# Month.net
KiCad netlist of a schematic drawn in Altium Designer
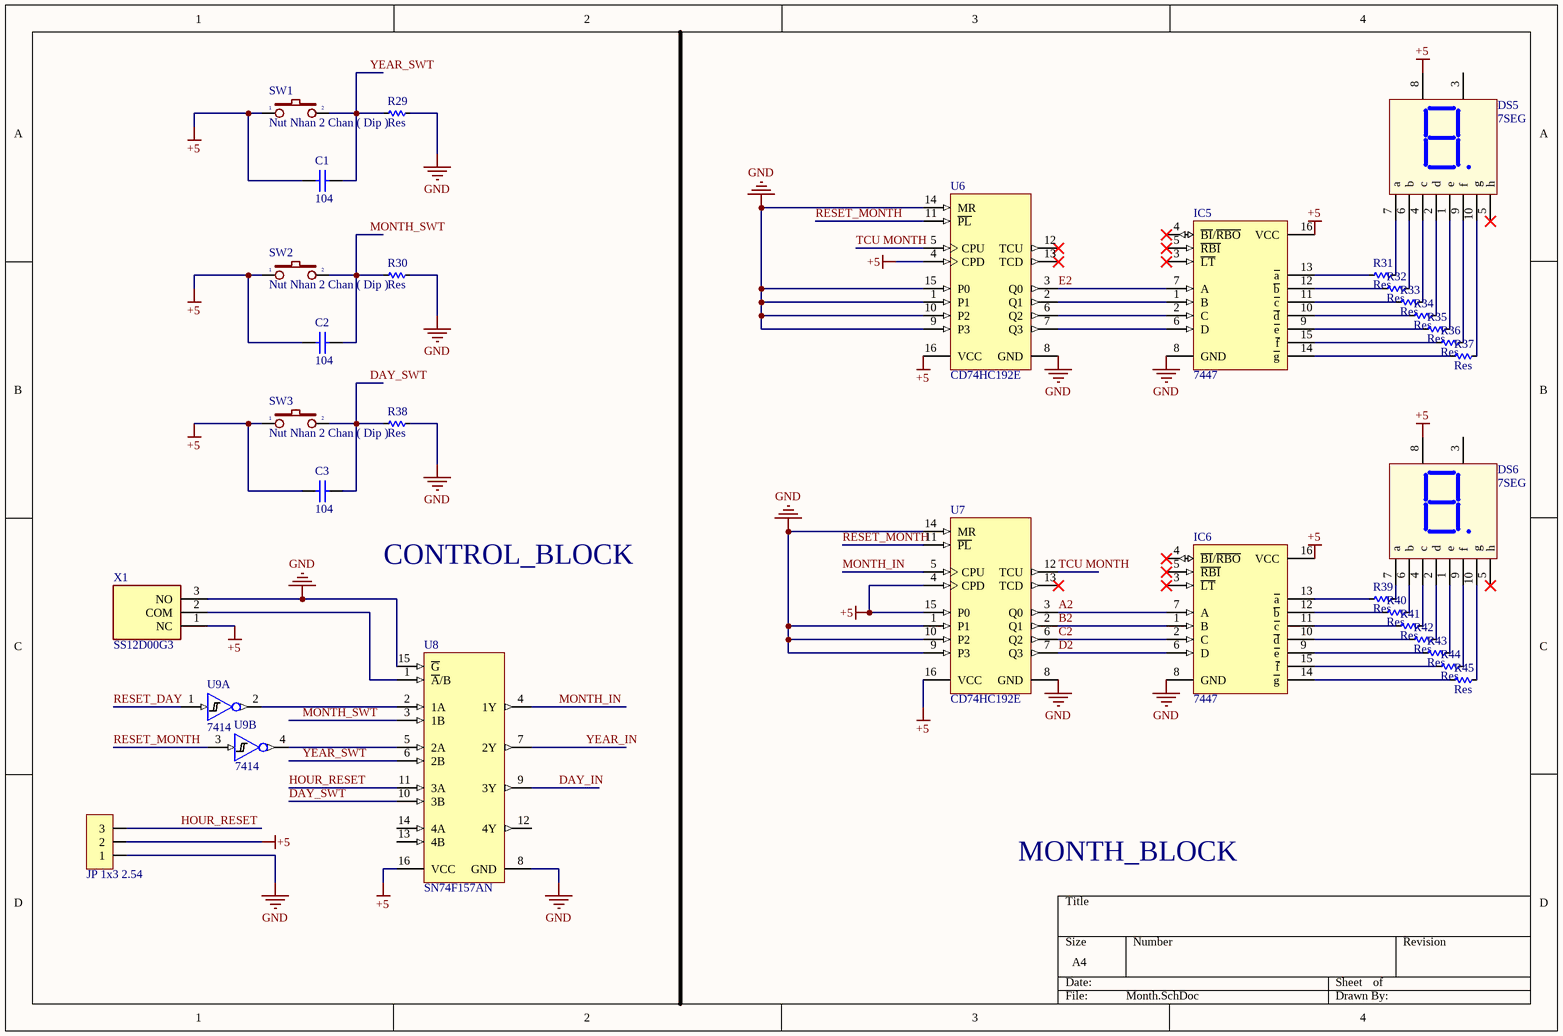
[diagram p0: Month.SchDoc]

(export (version "E")
  (design (tool "Eeschema 10.0.6"))
  (components
    (comp (ref "C1")
      (value "104")
      (footprint "tu gom")
      (description "Cắm")
      (libsource (lib "Tu dien") (part "Tu gom 104 50V"))
    )
    (comp (ref "C2")
      (value "104")
      (footprint "tu gom")
      (description "Cắm")
      (libsource (lib "Tu dien") (part "Tu gom 104 50V"))
    )
    (comp (ref "C3")
      (value "104")
      (footprint "tu gom")
      (description "Cắm")
      (libsource (lib "Tu dien") (part "Tu gom 104 50V"))
    )
    (comp (ref "DS5")
      (value "7SEG")
      (footprint "LED7SEG-1-0.56")
      (description "14.2 mm General Purpose Blue 7-Segment Display: CC, RH DP, Gray Surface")
      (fields (field (name "PUBLISHER") "Altium Limited"))
      (libsource (lib "Clock_Schlib1") (part "LED7SEG-1"))
    )
    (comp (ref "DS6")
      (value "7SEG")
      (footprint "LED7SEG-1-0.56")
      (description "14.2 mm General Purpose Blue 7-Segment Display: CC, RH DP, Gray Surface")
      (fields (field (name "PUBLISHER") "Altium Limited"))
      (libsource (lib "Clock_Schlib1") (part "LED7SEG-1"))
    )
    (comp (ref "IC5")
      (value "7447")
      (footprint "DIP16")
      (description "BCD to 7-Segment Decoder/Driver")
      (libsource (lib "Clock_Schlib1") (part "7447"))
    )
    (comp (ref "IC6")
      (value "7447")
      (footprint "DIP16")
      (description "BCD to 7-Segment Decoder/Driver")
      (libsource (lib "Clock_Schlib1") (part "7447"))
    )
    (comp (ref "JP1")
      (value "JP 1x3 2.54")
      (footprint "JP 1x3 CT")
      (description "Cắm")
      (libsource (lib "Jump") (part "JP 1x3 2.54 Cai Thang"))
    )
    (comp (ref "R29")
      (value "Res")
      (footprint "RES-1/4W")
      (fields
        (field (name "MANUFACTURER") "Generic Components")
        (field (name "PUBLISHER") "Altium Hobart Technology Centre")
      )
      (libsource (lib "Clock_Schlib1") (part "Res"))
    )
    (comp (ref "R30")
      (value "Res")
      (footprint "RES-1/4W")
      (fields
        (field (name "MANUFACTURER") "Generic Components")
        (field (name "PUBLISHER") "Altium Hobart Technology Centre")
      )
      (libsource (lib "Clock_Schlib1") (part "Res"))
    )
    (comp (ref "R31")
      (value "Res")
      (footprint "RES-1/4W")
      (fields
        (field (name "MANUFACTURER") "Generic Components")
        (field (name "PUBLISHER") "Altium Hobart Technology Centre")
      )
      (libsource (lib "Clock_Schlib1") (part "Res"))
    )
    (comp (ref "R32")
      (value "Res")
      (footprint "RES-1/4W")
      (fields
        (field (name "MANUFACTURER") "Generic Components")
        (field (name "PUBLISHER") "Altium Hobart Technology Centre")
      )
      (libsource (lib "Clock_Schlib1") (part "Res"))
    )
    (comp (ref "R33")
      (value "Res")
      (footprint "RES-1/4W")
      (fields
        (field (name "MANUFACTURER") "Generic Components")
        (field (name "PUBLISHER") "Altium Hobart Technology Centre")
      )
      (libsource (lib "Clock_Schlib1") (part "Res"))
    )
    (comp (ref "R34")
      (value "Res")
      (footprint "RES-1/4W")
      (fields
        (field (name "MANUFACTURER") "Generic Components")
        (field (name "PUBLISHER") "Altium Hobart Technology Centre")
      )
      (libsource (lib "Clock_Schlib1") (part "Res"))
    )
    (comp (ref "R35")
      (value "Res")
      (footprint "RES-1/4W")
      (fields
        (field (name "MANUFACTURER") "Generic Components")
        (field (name "PUBLISHER") "Altium Hobart Technology Centre")
      )
      (libsource (lib "Clock_Schlib1") (part "Res"))
    )
    (comp (ref "R36")
      (value "Res")
      (footprint "RES-1/4W")
      (fields
        (field (name "MANUFACTURER") "Generic Components")
        (field (name "PUBLISHER") "Altium Hobart Technology Centre")
      )
      (libsource (lib "Clock_Schlib1") (part "Res"))
    )
    (comp (ref "R37")
      (value "Res")
      (footprint "RES-1/4W")
      (fields
        (field (name "MANUFACTURER") "Generic Components")
        (field (name "PUBLISHER") "Altium Hobart Technology Centre")
      )
      (libsource (lib "Clock_Schlib1") (part "Res"))
    )
    (comp (ref "R38")
      (value "Res")
      (footprint "RES-1/4W")
      (fields
        (field (name "MANUFACTURER") "Generic Components")
        (field (name "PUBLISHER") "Altium Hobart Technology Centre")
      )
      (libsource (lib "Clock_Schlib1") (part "Res"))
    )
    (comp (ref "R39")
      (value "Res")
      (footprint "RES-1/4W")
      (fields
        (field (name "MANUFACTURER") "Generic Components")
        (field (name "PUBLISHER") "Altium Hobart Technology Centre")
      )
      (libsource (lib "Clock_Schlib1") (part "Res"))
    )
    (comp (ref "R40")
      (value "Res")
      (footprint "RES-1/4W")
      (fields
        (field (name "MANUFACTURER") "Generic Components")
        (field (name "PUBLISHER") "Altium Hobart Technology Centre")
      )
      (libsource (lib "Clock_Schlib1") (part "Res"))
    )
    (comp (ref "R41")
      (value "Res")
      (footprint "RES-1/4W")
      (fields
        (field (name "MANUFACTURER") "Generic Components")
        (field (name "PUBLISHER") "Altium Hobart Technology Centre")
      )
      (libsource (lib "Clock_Schlib1") (part "Res"))
    )
    (comp (ref "R42")
      (value "Res")
      (footprint "RES-1/4W")
      (fields
        (field (name "MANUFACTURER") "Generic Components")
        (field (name "PUBLISHER") "Altium Hobart Technology Centre")
      )
      (libsource (lib "Clock_Schlib1") (part "Res"))
    )
    (comp (ref "R43")
      (value "Res")
      (footprint "RES-1/4W")
      (fields
        (field (name "MANUFACTURER") "Generic Components")
        (field (name "PUBLISHER") "Altium Hobart Technology Centre")
      )
      (libsource (lib "Clock_Schlib1") (part "Res"))
    )
    (comp (ref "R44")
      (value "Res")
      (footprint "RES-1/4W")
      (fields
        (field (name "MANUFACTURER") "Generic Components")
        (field (name "PUBLISHER") "Altium Hobart Technology Centre")
      )
      (libsource (lib "Clock_Schlib1") (part "Res"))
    )
    (comp (ref "R45")
      (value "Res")
      (footprint "RES-1/4W")
      (fields
        (field (name "MANUFACTURER") "Generic Components")
        (field (name "PUBLISHER") "Altium Hobart Technology Centre")
      )
      (libsource (lib "Clock_Schlib1") (part "Res"))
    )
    (comp (ref "SW1")
      (value "Nut Nhan 2 Chan ( Dip )")
      (footprint "SW2")
      (description "Cắm")
      (libsource (lib "THU VIEN SCH") (part "Nut Nhan 2 Chan ( Dip )"))
    )
    (comp (ref "SW2")
      (value "Nut Nhan 2 Chan ( Dip )")
      (footprint "SW2")
      (description "Cắm")
      (libsource (lib "THU VIEN SCH") (part "Nut Nhan 2 Chan ( Dip )"))
    )
    (comp (ref "SW3")
      (value "Nut Nhan 2 Chan ( Dip )")
      (footprint "SW2")
      (description "Cắm")
      (libsource (lib "THU VIEN SCH") (part "Nut Nhan 2 Chan ( Dip )"))
    )
    (comp (ref "U6")
      (value "CD74HC192E")
      (footprint "N0016A")
      (fields
        (field (name "GENERIC PART NUMBER") "CD74HC192")
        (field (name "MANUFACTURER") "Texas Instruments")
      )
      (libsource (lib "Clock_Schlib1") (part "74192"))
    )
    (comp (ref "U7")
      (value "CD74HC192E")
      (footprint "N0016A")
      (fields
        (field (name "GENERIC PART NUMBER") "CD74HC192")
        (field (name "MANUFACTURER") "Texas Instruments")
      )
      (libsource (lib "Clock_Schlib1") (part "74192"))
    )
    (comp (ref "U8")
      (value "SN74F157AN")
      (footprint "N0016A")
      (description "Quadruple 2-Line To 1-Line Data Selectors/Multiplexers, N0016A, TUBE")
      (fields
        (field (name "MANUFACTURER") "Texas Instruments")
        (field (name "GENERIC PART NUMBER") "SN74F157A")
      )
      (libsource (lib "Altium Content Vault") (part "TI-XXX4XXXX15XX-16"))
    )
    (comp (ref "U9")
      (value "7414")
      (footprint "DIP14")
      (description "IC, M74HC04M, Hex Inverter, SO-14")
      (libsource (lib "Clock_Schlib1") (part "7414"))
    )
    (comp (ref "X1")
      (value "SS12D00G3")
      (footprint "SS12D00G3")
      (description "3 Pin Toggle Switch")
      (libsource (lib "Clock_Schlib1") (part "SS12D00G3"))
    )
  )
  (nets
    (net (code "1") (name "+5") (class "Default")
      (node (ref "C1") (pin "2") (pinfunction "2_2") (pintype "passive"))
      (node (ref "C2") (pin "2") (pinfunction "2_2") (pintype "passive"))
      (node (ref "C3") (pin "2") (pinfunction "2_2") (pintype "passive"))
      (node (ref "DS5") (pin "8") (pinfunction "Vcc_8") (pintype "passive"))
      (node (ref "DS6") (pin "8") (pinfunction "Vcc_8") (pintype "passive"))
      (node (ref "IC5") (pin "16") (pinfunction "VCC_16") (pintype "power_in"))
      (node (ref "IC6") (pin "16") (pinfunction "VCC_16") (pintype "power_in"))
      (node (ref "JP1") (pin "2") (pinfunction "2_2") (pintype "passive"))
      (node (ref "SW1") (pin "1") (pinfunction "1_1") (pintype "passive"))
      (node (ref "SW2") (pin "1") (pinfunction "1_1") (pintype "passive"))
      (node (ref "SW3") (pin "1") (pinfunction "1_1") (pintype "passive"))
      (node (ref "U6") (pin "16") (pinfunction "VCC_16") (pintype "power_in"))
      (node (ref "U6") (pin "4") (pinfunction "CPD_4") (pintype "input"))
      (node (ref "U7") (pin "15") (pinfunction "P0_15") (pintype "input"))
      (node (ref "U7") (pin "16") (pinfunction "VCC_16") (pintype "power_in"))
      (node (ref "U7") (pin "4") (pinfunction "CPD_4") (pintype "input"))
      (node (ref "U8") (pin "16") (pinfunction "VCC_16") (pintype "power_in"))
      (node (ref "X1") (pin "1") (pinfunction "NC_1") (pintype "passive"))
    )
    (net (code "2") (name "/A2") (class "Default")
      (node (ref "IC6") (pin "7") (pinfunction "A_7") (pintype "input"))
      (node (ref "U7") (pin "3") (pinfunction "Q0_3") (pintype "output"))
    )
    (net (code "3") (name "/B2") (class "Default")
      (node (ref "IC6") (pin "1") (pinfunction "B_1") (pintype "input"))
      (node (ref "U7") (pin "2") (pinfunction "Q1_2") (pintype "output"))
    )
    (net (code "4") (name "/C2") (class "Default")
      (node (ref "IC6") (pin "2") (pinfunction "C_2") (pintype "input"))
      (node (ref "U7") (pin "6") (pinfunction "Q2_6") (pintype "output"))
    )
    (net (code "5") (name "/D2") (class "Default")
      (node (ref "IC6") (pin "6") (pinfunction "D_6") (pintype "input"))
      (node (ref "U7") (pin "7") (pinfunction "Q3_7") (pintype "output"))
    )
    (net (code "6") (name "/DAY_IN") (class "Default")
      (node (ref "U8") (pin "9") (pinfunction "3Y_9") (pintype "output"))
    )
    (net (code "7") (name "/DAY_SWT") (class "Default")
      (node (ref "C3") (pin "1") (pinfunction "1_1") (pintype "passive"))
      (node (ref "R38") (pin "2") (pinfunction "2_2") (pintype "passive"))
      (node (ref "SW3") (pin "2") (pinfunction "2_2") (pintype "passive"))
      (node (ref "U8") (pin "10") (pinfunction "3B_10") (pintype "input"))
    )
    (net (code "8") (name "/E2") (class "Default")
      (node (ref "IC5") (pin "7") (pinfunction "A_7") (pintype "input"))
      (node (ref "U6") (pin "3") (pinfunction "Q0_3") (pintype "output"))
    )
    (net (code "9") (name "/HOUR_RESET") (class "Default")
      (node (ref "JP1") (pin "3") (pinfunction "3_3") (pintype "passive"))
      (node (ref "U8") (pin "11") (pinfunction "3A_11") (pintype "input"))
    )
    (net (code "10") (name "/MONTH_IN") (class "Default")
      (node (ref "U7") (pin "5") (pinfunction "CPU_5") (pintype "input"))
      (node (ref "U8") (pin "4") (pinfunction "1Y_4") (pintype "output"))
    )
    (net (code "11") (name "/MONTH_SWT") (class "Default")
      (node (ref "C2") (pin "1") (pinfunction "1_1") (pintype "passive"))
      (node (ref "R30") (pin "2") (pinfunction "2_2") (pintype "passive"))
      (node (ref "SW2") (pin "2") (pinfunction "2_2") (pintype "passive"))
      (node (ref "U8") (pin "3") (pinfunction "1B_3") (pintype "input"))
    )
    (net (code "12") (name "/RESET_DAY") (class "Default")
      (node (ref "U9") (pin "1") (pinfunction "A_1") (pintype "input"))
    )
    (net (code "13") (name "/RESET_MONTH") (class "Default")
      (node (ref "U6") (pin "11") (pinfunction "~{PL}_11") (pintype "input"))
      (node (ref "U7") (pin "11") (pinfunction "~{PL}_11") (pintype "input"))
      (node (ref "U9") (pin "3") (pinfunction "A_3") (pintype "input"))
    )
    (net (code "14") (name "/TCU MONTH") (class "Default")
      (node (ref "U6") (pin "5") (pinfunction "CPU_5") (pintype "input"))
      (node (ref "U7") (pin "12") (pinfunction "TCU_12") (pintype "output"))
    )
    (net (code "15") (name "/YEAR_IN") (class "Default")
      (node (ref "U8") (pin "7") (pinfunction "2Y_7") (pintype "output"))
    )
    (net (code "16") (name "/YEAR_SWT") (class "Default")
      (node (ref "C1") (pin "1") (pinfunction "1_1") (pintype "passive"))
      (node (ref "R29") (pin "2") (pinfunction "2_2") (pintype "passive"))
      (node (ref "SW1") (pin "2") (pinfunction "2_2") (pintype "passive"))
      (node (ref "U8") (pin "6") (pinfunction "2B_6") (pintype "input"))
    )
    (net (code "17") (name "GND") (class "Default")
      (node (ref "IC5") (pin "8") (pinfunction "GND_8") (pintype "power_in"))
      (node (ref "IC6") (pin "8") (pinfunction "GND_8") (pintype "power_in"))
      (node (ref "JP1") (pin "1") (pinfunction "1_1") (pintype "passive"))
      (node (ref "R29") (pin "1") (pinfunction "1_1") (pintype "passive"))
      (node (ref "R30") (pin "1") (pinfunction "1_1") (pintype "passive"))
      (node (ref "R38") (pin "1") (pinfunction "1_1") (pintype "passive"))
      (node (ref "U6") (pin "1") (pinfunction "P1_1") (pintype "input"))
      (node (ref "U6") (pin "10") (pinfunction "P2_10") (pintype "input"))
      (node (ref "U6") (pin "14") (pinfunction "MR_14") (pintype "input"))
      (node (ref "U6") (pin "15") (pinfunction "P0_15") (pintype "input"))
      (node (ref "U6") (pin "8") (pinfunction "GND_8") (pintype "power_in"))
      (node (ref "U6") (pin "9") (pinfunction "P3_9") (pintype "input"))
      (node (ref "U7") (pin "1") (pinfunction "P1_1") (pintype "input"))
      (node (ref "U7") (pin "10") (pinfunction "P2_10") (pintype "input"))
      (node (ref "U7") (pin "14") (pinfunction "MR_14") (pintype "input"))
      (node (ref "U7") (pin "8") (pinfunction "GND_8") (pintype "power_in"))
      (node (ref "U7") (pin "9") (pinfunction "P3_9") (pintype "input"))
      (node (ref "U8") (pin "15") (pinfunction "~{G}_15") (pintype "input"))
      (node (ref "U8") (pin "8") (pinfunction "GND_8") (pintype "power_in"))
      (node (ref "X1") (pin "3") (pinfunction "NO_3") (pintype "passive"))
    )
    (net (code "18") (name "Net-(DS5-a)") (class "Default")
      (node (ref "DS5") (pin "7") (pinfunction "a_7") (pintype "passive"))
      (node (ref "R31") (pin "1") (pinfunction "1_1") (pintype "passive"))
    )
    (net (code "19") (name "Net-(DS5-b)") (class "Default")
      (node (ref "DS5") (pin "6") (pinfunction "b_6") (pintype "passive"))
      (node (ref "R32") (pin "1") (pinfunction "1_1") (pintype "passive"))
    )
    (net (code "20") (name "Net-(DS5-c)") (class "Default")
      (node (ref "DS5") (pin "4") (pinfunction "c_4") (pintype "passive"))
      (node (ref "R33") (pin "1") (pinfunction "1_1") (pintype "passive"))
    )
    (net (code "21") (name "Net-(DS5-d)") (class "Default")
      (node (ref "DS5") (pin "2") (pinfunction "d_2") (pintype "passive"))
      (node (ref "R34") (pin "1") (pinfunction "1_1") (pintype "passive"))
    )
    (net (code "22") (name "Net-(DS5-e)") (class "Default")
      (node (ref "DS5") (pin "1") (pinfunction "e_1") (pintype "passive"))
      (node (ref "R35") (pin "1") (pinfunction "1_1") (pintype "passive"))
    )
    (net (code "23") (name "Net-(DS5-f)") (class "Default")
      (node (ref "DS5") (pin "9") (pinfunction "f_9") (pintype "passive"))
      (node (ref "R36") (pin "1") (pinfunction "1_1") (pintype "passive"))
    )
    (net (code "24") (name "Net-(DS5-g)") (class "Default")
      (node (ref "DS5") (pin "10") (pinfunction "g_10") (pintype "passive"))
      (node (ref "R37") (pin "1") (pinfunction "1_1") (pintype "passive"))
    )
    (net (code "25") (name "Net-(DS6-a)") (class "Default")
      (node (ref "DS6") (pin "7") (pinfunction "a_7") (pintype "passive"))
      (node (ref "R39") (pin "1") (pinfunction "1_1") (pintype "passive"))
    )
    (net (code "26") (name "Net-(DS6-b)") (class "Default")
      (node (ref "DS6") (pin "6") (pinfunction "b_6") (pintype "passive"))
      (node (ref "R40") (pin "1") (pinfunction "1_1") (pintype "passive"))
    )
    (net (code "27") (name "Net-(DS6-c)") (class "Default")
      (node (ref "DS6") (pin "4") (pinfunction "c_4") (pintype "passive"))
      (node (ref "R41") (pin "1") (pinfunction "1_1") (pintype "passive"))
    )
    (net (code "28") (name "Net-(DS6-d)") (class "Default")
      (node (ref "DS6") (pin "2") (pinfunction "d_2") (pintype "passive"))
      (node (ref "R42") (pin "1") (pinfunction "1_1") (pintype "passive"))
    )
    (net (code "29") (name "Net-(DS6-e)") (class "Default")
      (node (ref "DS6") (pin "1") (pinfunction "e_1") (pintype "passive"))
      (node (ref "R43") (pin "1") (pinfunction "1_1") (pintype "passive"))
    )
    (net (code "30") (name "Net-(DS6-f)") (class "Default")
      (node (ref "DS6") (pin "9") (pinfunction "f_9") (pintype "passive"))
      (node (ref "R44") (pin "1") (pinfunction "1_1") (pintype "passive"))
    )
    (net (code "31") (name "Net-(DS6-g)") (class "Default")
      (node (ref "DS6") (pin "10") (pinfunction "g_10") (pintype "passive"))
      (node (ref "R45") (pin "1") (pinfunction "1_1") (pintype "passive"))
    )
    (net (code "32") (name "Net-(IC5-B)") (class "Default")
      (node (ref "IC5") (pin "1") (pinfunction "B_1") (pintype "input"))
      (node (ref "U6") (pin "2") (pinfunction "Q1_2") (pintype "output"))
    )
    (net (code "33") (name "Net-(IC5-C)") (class "Default")
      (node (ref "IC5") (pin "2") (pinfunction "C_2") (pintype "input"))
      (node (ref "U6") (pin "6") (pinfunction "Q2_6") (pintype "output"))
    )
    (net (code "34") (name "Net-(IC5-D)") (class "Default")
      (node (ref "IC5") (pin "6") (pinfunction "D_6") (pintype "input"))
      (node (ref "U6") (pin "7") (pinfunction "Q3_7") (pintype "output"))
    )
    (net (code "35") (name "Net-(IC5-~{a})") (class "Default")
      (node (ref "IC5") (pin "13") (pinfunction "~{a}_13") (pintype "open_collector"))
      (node (ref "R31") (pin "2") (pinfunction "2_2") (pintype "passive"))
    )
    (net (code "36") (name "Net-(IC5-~{b})") (class "Default")
      (node (ref "IC5") (pin "12") (pinfunction "~{b}_12") (pintype "open_collector"))
      (node (ref "R32") (pin "2") (pinfunction "2_2") (pintype "passive"))
    )
    (net (code "37") (name "Net-(IC5-~{c})") (class "Default")
      (node (ref "IC5") (pin "11") (pinfunction "~{c}_11") (pintype "open_collector"))
      (node (ref "R33") (pin "2") (pinfunction "2_2") (pintype "passive"))
    )
    (net (code "38") (name "Net-(IC5-~{d})") (class "Default")
      (node (ref "IC5") (pin "10") (pinfunction "~{d}_10") (pintype "open_collector"))
      (node (ref "R34") (pin "2") (pinfunction "2_2") (pintype "passive"))
    )
    (net (code "39") (name "Net-(IC5-~{e})") (class "Default")
      (node (ref "IC5") (pin "9") (pinfunction "~{e}_9") (pintype "open_collector"))
      (node (ref "R35") (pin "2") (pinfunction "2_2") (pintype "passive"))
    )
    (net (code "40") (name "Net-(IC5-~{f})") (class "Default")
      (node (ref "IC5") (pin "15") (pinfunction "~{f}_15") (pintype "open_collector"))
      (node (ref "R36") (pin "2") (pinfunction "2_2") (pintype "passive"))
    )
    (net (code "41") (name "Net-(IC5-~{g})") (class "Default")
      (node (ref "IC5") (pin "14") (pinfunction "~{g}_14") (pintype "open_collector"))
      (node (ref "R37") (pin "2") (pinfunction "2_2") (pintype "passive"))
    )
    (net (code "42") (name "Net-(IC6-~{a})") (class "Default")
      (node (ref "IC6") (pin "13") (pinfunction "~{a}_13") (pintype "open_collector"))
      (node (ref "R39") (pin "2") (pinfunction "2_2") (pintype "passive"))
    )
    (net (code "43") (name "Net-(IC6-~{b})") (class "Default")
      (node (ref "IC6") (pin "12") (pinfunction "~{b}_12") (pintype "open_collector"))
      (node (ref "R40") (pin "2") (pinfunction "2_2") (pintype "passive"))
    )
    (net (code "44") (name "Net-(IC6-~{c})") (class "Default")
      (node (ref "IC6") (pin "11") (pinfunction "~{c}_11") (pintype "open_collector"))
      (node (ref "R41") (pin "2") (pinfunction "2_2") (pintype "passive"))
    )
    (net (code "45") (name "Net-(IC6-~{d})") (class "Default")
      (node (ref "IC6") (pin "10") (pinfunction "~{d}_10") (pintype "open_collector"))
      (node (ref "R42") (pin "2") (pinfunction "2_2") (pintype "passive"))
    )
    (net (code "46") (name "Net-(IC6-~{e})") (class "Default")
      (node (ref "IC6") (pin "9") (pinfunction "~{e}_9") (pintype "open_collector"))
      (node (ref "R43") (pin "2") (pinfunction "2_2") (pintype "passive"))
    )
    (net (code "47") (name "Net-(IC6-~{f})") (class "Default")
      (node (ref "IC6") (pin "15") (pinfunction "~{f}_15") (pintype "open_collector"))
      (node (ref "R44") (pin "2") (pinfunction "2_2") (pintype "passive"))
    )
    (net (code "48") (name "Net-(IC6-~{g})") (class "Default")
      (node (ref "IC6") (pin "14") (pinfunction "~{g}_14") (pintype "open_collector"))
      (node (ref "R45") (pin "2") (pinfunction "2_2") (pintype "passive"))
    )
    (net (code "49") (name "Net-(U8-1A)") (class "Default")
      (node (ref "U8") (pin "2") (pinfunction "1A_2") (pintype "input"))
      (node (ref "U9") (pin "2") (pinfunction "Y_2") (pintype "output"))
    )
    (net (code "50") (name "Net-(U8-2A)") (class "Default")
      (node (ref "U8") (pin "5") (pinfunction "2A_5") (pintype "input"))
      (node (ref "U9") (pin "4") (pinfunction "Y_4") (pintype "output"))
    )
    (net (code "51") (name "Net-(U8-~{A}{slash}B)") (class "Default")
      (node (ref "U8") (pin "1") (pinfunction "~{A}/B_1") (pintype "input"))
      (node (ref "X1") (pin "2") (pinfunction "COM_2") (pintype "passive"))
    )
    (net (code "52") (name "unconnected-(DS5-Vcc-Pad3)") (class "Default")
      (node (ref "DS5") (pin "3") (pinfunction "Vcc_3") (pintype "passive"))
    )
    (net (code "53") (name "unconnected-(DS5-h-Pad5)") (class "Default")
      (node (ref "DS5") (pin "5") (pinfunction "h_5") (pintype "passive+no_connect"))
    )
    (net (code "54") (name "unconnected-(DS6-Vcc-Pad3)") (class "Default")
      (node (ref "DS6") (pin "3") (pinfunction "Vcc_3") (pintype "passive"))
    )
    (net (code "55") (name "unconnected-(DS6-h-Pad5)") (class "Default")
      (node (ref "DS6") (pin "5") (pinfunction "h_5") (pintype "passive+no_connect"))
    )
    (net (code "56") (name "unconnected-(IC5-~{BI}{slash}~{RBO}-Pad4)") (class "Default")
      (node (ref "IC5") (pin "4") (pinfunction "~{BI}/~{RBO}_4") (pintype "bidirectional+no_connect"))
    )
    (net (code "57") (name "unconnected-(IC5-~{LT}-Pad3)") (class "Default")
      (node (ref "IC5") (pin "3") (pinfunction "~{LT}_3") (pintype "input+no_connect"))
    )
    (net (code "58") (name "unconnected-(IC5-~{RBI}-Pad5)") (class "Default")
      (node (ref "IC5") (pin "5") (pinfunction "~{RBI}_5") (pintype "input+no_connect"))
    )
    (net (code "59") (name "unconnected-(IC6-~{BI}{slash}~{RBO}-Pad4)") (class "Default")
      (node (ref "IC6") (pin "4") (pinfunction "~{BI}/~{RBO}_4") (pintype "bidirectional+no_connect"))
    )
    (net (code "60") (name "unconnected-(IC6-~{LT}-Pad3)") (class "Default")
      (node (ref "IC6") (pin "3") (pinfunction "~{LT}_3") (pintype "input+no_connect"))
    )
    (net (code "61") (name "unconnected-(IC6-~{RBI}-Pad5)") (class "Default")
      (node (ref "IC6") (pin "5") (pinfunction "~{RBI}_5") (pintype "input+no_connect"))
    )
    (net (code "62") (name "unconnected-(U6-TCD-Pad13)") (class "Default")
      (node (ref "U6") (pin "13") (pinfunction "TCD_13") (pintype "output+no_connect"))
    )
    (net (code "63") (name "unconnected-(U6-TCU-Pad12)") (class "Default")
      (node (ref "U6") (pin "12") (pinfunction "TCU_12") (pintype "output+no_connect"))
    )
    (net (code "64") (name "unconnected-(U7-TCD-Pad13)") (class "Default")
      (node (ref "U7") (pin "13") (pinfunction "TCD_13") (pintype "output+no_connect"))
    )
    (net (code "65") (name "unconnected-(U8-4A-Pad14)") (class "Default")
      (node (ref "U8") (pin "14") (pinfunction "4A_14") (pintype "input"))
    )
    (net (code "66") (name "unconnected-(U8-4B-Pad13)") (class "Default")
      (node (ref "U8") (pin "13") (pinfunction "4B_13") (pintype "input"))
    )
    (net (code "67") (name "unconnected-(U8-4Y-Pad12)") (class "Default")
      (node (ref "U8") (pin "12") (pinfunction "4Y_12") (pintype "output"))
    )
  )
)
